# KSS3.net
KiCad netlist of a schematic drawn in Altium Designer
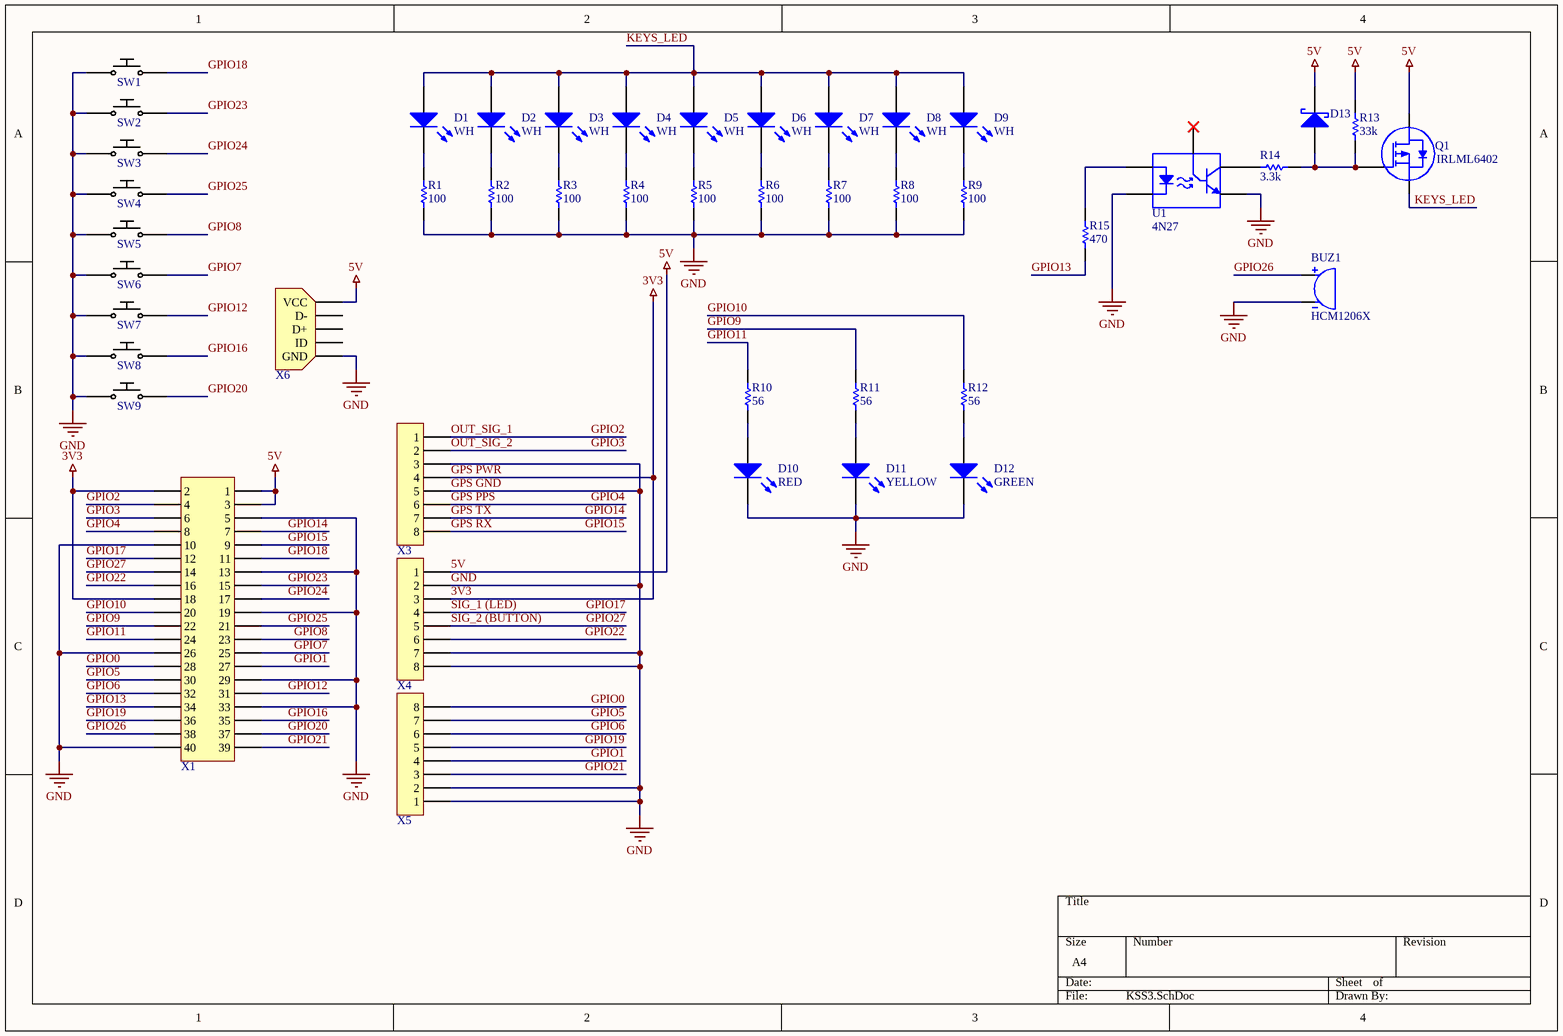
[diagram p0: KSS3.SchDoc]

(export (version "E")
  (design (tool "Eeschema 10.0.6"))
  (components
    (comp (ref "BUZ1")
      (value "HCM1206X")
      (footprint "HCM1206X")
      (description "Buzzer")
      (libsource (lib "COMPONENTS_2022") (part "HCM1206X"))
    )
    (comp (ref "D1")
      (value "WH")
      (footprint "LED_1206")
      (libsource (lib "COMPONENTS_2022") (part "Diode LED"))
    )
    (comp (ref "D2")
      (value "WH")
      (footprint "LED_1206")
      (libsource (lib "COMPONENTS_2022") (part "Diode LED"))
    )
    (comp (ref "D3")
      (value "WH")
      (footprint "LED_1206")
      (libsource (lib "COMPONENTS_2022") (part "Diode LED"))
    )
    (comp (ref "D4")
      (value "WH")
      (footprint "LED_1206")
      (libsource (lib "COMPONENTS_2022") (part "Diode LED"))
    )
    (comp (ref "D5")
      (value "WH")
      (footprint "LED_1206")
      (libsource (lib "COMPONENTS_2022") (part "Diode LED"))
    )
    (comp (ref "D6")
      (value "WH")
      (footprint "LED_1206")
      (libsource (lib "COMPONENTS_2022") (part "Diode LED"))
    )
    (comp (ref "D7")
      (value "WH")
      (footprint "LED_1206")
      (libsource (lib "COMPONENTS_2022") (part "Diode LED"))
    )
    (comp (ref "D8")
      (value "WH")
      (footprint "LED_1206")
      (libsource (lib "COMPONENTS_2022") (part "Diode LED"))
    )
    (comp (ref "D9")
      (value "WH")
      (footprint "LED_1206")
      (libsource (lib "COMPONENTS_2022") (part "Diode LED"))
    )
    (comp (ref "D10")
      (value "RED")
      (footprint "LED_1206")
      (libsource (lib "COMPONENTS_2022") (part "Diode LED"))
    )
    (comp (ref "D11")
      (value "YELLOW")
      (footprint "LED_1206")
      (libsource (lib "COMPONENTS_2022") (part "Diode LED"))
    )
    (comp (ref "D12")
      (value "GREEN")
      (footprint "LED_1206")
      (libsource (lib "COMPONENTS_2022") (part "Diode LED"))
    )
    (comp (ref "D13")
      (value "SS14")
      (footprint "SMA/DO-214AC")
      (description "Schottky")
      (libsource (lib "COMPONENTS_2022") (part "SS14"))
    )
    (comp (ref "Q1")
      (value "IRLML6402")
      (footprint "SOT23_3_PIN")
      (description "P-MOSFET")
      (libsource (lib "COMPONENTS_2022") (part "IRLML6402"))
    )
    (comp (ref "R1")
      (value "Resistor")
      (footprint "RES 1206")
      (fields (field (name "RESISTANCE") "100"))
      (libsource (lib "COMPONENTS_2022") (part "Resistor"))
    )
    (comp (ref "R2")
      (value "Resistor")
      (footprint "RES 1206")
      (fields (field (name "RESISTANCE") "100"))
      (libsource (lib "COMPONENTS_2022") (part "Resistor"))
    )
    (comp (ref "R3")
      (value "Resistor")
      (footprint "RES 1206")
      (fields (field (name "RESISTANCE") "100"))
      (libsource (lib "COMPONENTS_2022") (part "Resistor"))
    )
    (comp (ref "R4")
      (value "Resistor")
      (footprint "RES 1206")
      (fields (field (name "RESISTANCE") "100"))
      (libsource (lib "COMPONENTS_2022") (part "Resistor"))
    )
    (comp (ref "R5")
      (value "Resistor")
      (footprint "RES 1206")
      (fields (field (name "RESISTANCE") "100"))
      (libsource (lib "COMPONENTS_2022") (part "Resistor"))
    )
    (comp (ref "R6")
      (value "Resistor")
      (footprint "RES 1206")
      (fields (field (name "RESISTANCE") "100"))
      (libsource (lib "COMPONENTS_2022") (part "Resistor"))
    )
    (comp (ref "R7")
      (value "Resistor")
      (footprint "RES 1206")
      (fields (field (name "RESISTANCE") "100"))
      (libsource (lib "COMPONENTS_2022") (part "Resistor"))
    )
    (comp (ref "R8")
      (value "Resistor")
      (footprint "RES 1206")
      (fields (field (name "RESISTANCE") "100"))
      (libsource (lib "COMPONENTS_2022") (part "Resistor"))
    )
    (comp (ref "R9")
      (value "Resistor")
      (footprint "RES 1206")
      (fields (field (name "RESISTANCE") "100"))
      (libsource (lib "COMPONENTS_2022") (part "Resistor"))
    )
    (comp (ref "R10")
      (value "Resistor")
      (footprint "RES 1206")
      (fields (field (name "RESISTANCE") "56"))
      (libsource (lib "COMPONENTS_2022") (part "Resistor"))
    )
    (comp (ref "R11")
      (value "Resistor")
      (footprint "RES 1206")
      (fields (field (name "RESISTANCE") "56"))
      (libsource (lib "COMPONENTS_2022") (part "Resistor"))
    )
    (comp (ref "R12")
      (value "Resistor")
      (footprint "RES 1206")
      (fields (field (name "RESISTANCE") "56"))
      (libsource (lib "COMPONENTS_2022") (part "Resistor"))
    )
    (comp (ref "R13")
      (value "Resistor")
      (footprint "RES 1206")
      (fields (field (name "RESISTANCE") "33k"))
      (libsource (lib "COMPONENTS_2022") (part "Resistor"))
    )
    (comp (ref "R14")
      (value "Resistor")
      (footprint "RES 1206")
      (fields (field (name "RESISTANCE") "3.3k"))
      (libsource (lib "COMPONENTS_2022") (part "Resistor"))
    )
    (comp (ref "R15")
      (value "Resistor")
      (footprint "RES 1206")
      (fields (field (name "RESISTANCE") "470"))
      (libsource (lib "COMPONENTS_2022") (part "Resistor"))
    )
    (comp (ref "SW1")
      (value "Pushbutton")
      (footprint "Key switch Outemu")
      (libsource (lib "COMPONENTS_2022") (part "Pushbutton"))
    )
    (comp (ref "SW2")
      (value "Pushbutton")
      (footprint "Key switch Outemu")
      (libsource (lib "COMPONENTS_2022") (part "Pushbutton"))
    )
    (comp (ref "SW3")
      (value "Pushbutton")
      (footprint "Key switch Outemu")
      (libsource (lib "COMPONENTS_2022") (part "Pushbutton"))
    )
    (comp (ref "SW4")
      (value "Pushbutton")
      (footprint "Key switch Outemu")
      (libsource (lib "COMPONENTS_2022") (part "Pushbutton"))
    )
    (comp (ref "SW5")
      (value "Pushbutton")
      (footprint "Key switch Outemu")
      (libsource (lib "COMPONENTS_2022") (part "Pushbutton"))
    )
    (comp (ref "SW6")
      (value "Pushbutton")
      (footprint "Key switch Outemu")
      (libsource (lib "COMPONENTS_2022") (part "Pushbutton"))
    )
    (comp (ref "SW7")
      (value "Pushbutton")
      (footprint "Key switch Outemu")
      (libsource (lib "COMPONENTS_2022") (part "Pushbutton"))
    )
    (comp (ref "SW8")
      (value "Pushbutton")
      (footprint "Key switch Outemu")
      (libsource (lib "COMPONENTS_2022") (part "Pushbutton"))
    )
    (comp (ref "SW9")
      (value "Pushbutton")
      (footprint "Key switch Outemu")
      (libsource (lib "COMPONENTS_2022") (part "Pushbutton"))
    )
    (comp (ref "U1")
      (value "4N27")
      (footprint "DIP6")
      (description "Optocoupler")
      (libsource (lib "COMPONENTS_2022") (part "4N27"))
    )
    (comp (ref "X1")
      (value "GoldPin_F_20x2")
      (footprint "GOLDPIN_F_20x2")
      (libsource (lib "COMPONENTS_2022") (part "GoldPin_F_20x2"))
    )
    (comp (ref "X3")
      (value "?")
      (footprint "SCREW_TERMINAL_X8 5,08mm")
      (libsource (lib "") (part "Connector x8_1"))
    )
    (comp (ref "X4")
      (value "?")
      (footprint "SCREW_TERMINAL_X8 5,08mm")
      (libsource (lib "") (part "Connector x8_1"))
    )
    (comp (ref "X5")
      (value "?")
      (footprint "SCREW_TERMINAL_X8 5,08mm")
      (libsource (lib "COMPONENTS_2022") (part "Connector x8"))
    )
    (comp (ref "X6")
      (value "USB_MICRO_B")
      (footprint "USB_MICRO_B_940 KEYSTONE")
      (libsource (lib "COMPONENTS_2022") (part "USB_MICRO_B"))
    )
  )
  (nets
    (net (code "1") (name "/GPIO0") (class "Default")
      (node (ref "X1") (pin "28") (pinfunction "28_28") (pintype "passive"))
      (node (ref "X5") (pin "8") (pinfunction "8_8") (pintype "passive"))
    )
    (net (code "2") (name "/GPIO1") (class "Default")
      (node (ref "X1") (pin "27") (pinfunction "27_27") (pintype "passive"))
      (node (ref "X5") (pin "4") (pinfunction "4_4") (pintype "passive"))
    )
    (net (code "3") (name "/GPIO2") (class "Default")
      (node (ref "X1") (pin "4") (pinfunction "4_4") (pintype "passive"))
      (node (ref "X3") (pin "1") (pinfunction "1_1") (pintype "passive"))
    )
    (net (code "4") (name "/GPIO3") (class "Default")
      (node (ref "X1") (pin "6") (pinfunction "6_6") (pintype "passive"))
      (node (ref "X3") (pin "2") (pinfunction "2_2") (pintype "passive"))
    )
    (net (code "5") (name "/GPIO4") (class "Default")
      (node (ref "X1") (pin "8") (pinfunction "8_8") (pintype "passive"))
      (node (ref "X3") (pin "6") (pinfunction "6_6") (pintype "passive"))
    )
    (net (code "6") (name "/GPIO5") (class "Default")
      (node (ref "X1") (pin "30") (pinfunction "30_30") (pintype "passive"))
      (node (ref "X5") (pin "7") (pinfunction "7_7") (pintype "passive"))
    )
    (net (code "7") (name "/GPIO6") (class "Default")
      (node (ref "X1") (pin "32") (pinfunction "32_32") (pintype "passive"))
      (node (ref "X5") (pin "6") (pinfunction "6_6") (pintype "passive"))
    )
    (net (code "8") (name "/GPIO7") (class "Default")
      (node (ref "SW6") (pin "2") (pinfunction "2_2") (pintype "passive"))
      (node (ref "X1") (pin "25") (pinfunction "25_25") (pintype "passive"))
    )
    (net (code "9") (name "/GPIO8") (class "Default")
      (node (ref "SW5") (pin "2") (pinfunction "2_2") (pintype "passive"))
      (node (ref "X1") (pin "23") (pinfunction "23_23") (pintype "passive"))
    )
    (net (code "10") (name "/GPIO9") (class "Default")
      (node (ref "R11") (pin "2") (pinfunction "2_2") (pintype "passive"))
      (node (ref "X1") (pin "22") (pinfunction "22_22") (pintype "passive"))
    )
    (net (code "11") (name "/GPIO10") (class "Default")
      (node (ref "R12") (pin "2") (pinfunction "2_2") (pintype "passive"))
      (node (ref "X1") (pin "20") (pinfunction "20_20") (pintype "passive"))
    )
    (net (code "12") (name "/GPIO11") (class "Default")
      (node (ref "R10") (pin "2") (pinfunction "2_2") (pintype "passive"))
      (node (ref "X1") (pin "24") (pinfunction "24_24") (pintype "passive"))
    )
    (net (code "13") (name "/GPIO12") (class "Default")
      (node (ref "SW7") (pin "2") (pinfunction "2_2") (pintype "passive"))
      (node (ref "X1") (pin "31") (pinfunction "31_31") (pintype "passive"))
    )
    (net (code "14") (name "/GPIO13") (class "Default")
      (node (ref "R15") (pin "1") (pinfunction "1_1") (pintype "passive"))
      (node (ref "X1") (pin "34") (pinfunction "34_34") (pintype "passive"))
    )
    (net (code "15") (name "/GPIO14") (class "Default")
      (node (ref "X1") (pin "7") (pinfunction "7_7") (pintype "passive"))
      (node (ref "X3") (pin "7") (pinfunction "7_7") (pintype "passive"))
    )
    (net (code "16") (name "/GPIO15") (class "Default")
      (node (ref "X1") (pin "9") (pinfunction "9_9") (pintype "passive"))
      (node (ref "X3") (pin "8") (pinfunction "8_8") (pintype "passive"))
    )
    (net (code "17") (name "/GPIO16") (class "Default")
      (node (ref "SW8") (pin "2") (pinfunction "2_2") (pintype "passive"))
      (node (ref "X1") (pin "35") (pinfunction "35_35") (pintype "passive"))
    )
    (net (code "18") (name "/GPIO17") (class "Default")
      (node (ref "X1") (pin "12") (pinfunction "12_12") (pintype "passive"))
      (node (ref "X4") (pin "4") (pinfunction "4_4") (pintype "passive"))
    )
    (net (code "19") (name "/GPIO18") (class "Default")
      (node (ref "SW1") (pin "2") (pinfunction "2_2") (pintype "passive"))
      (node (ref "X1") (pin "11") (pinfunction "11_11") (pintype "passive"))
    )
    (net (code "20") (name "/GPIO19") (class "Default")
      (node (ref "X1") (pin "36") (pinfunction "36_36") (pintype "passive"))
      (node (ref "X5") (pin "5") (pinfunction "5_5") (pintype "passive"))
    )
    (net (code "21") (name "/GPIO20") (class "Default")
      (node (ref "SW9") (pin "2") (pinfunction "2_2") (pintype "passive"))
      (node (ref "X1") (pin "37") (pinfunction "37_37") (pintype "passive"))
    )
    (net (code "22") (name "/GPIO21") (class "Default")
      (node (ref "X1") (pin "39") (pinfunction "39_39") (pintype "passive"))
      (node (ref "X5") (pin "3") (pinfunction "3_3") (pintype "passive"))
    )
    (net (code "23") (name "/GPIO22") (class "Default")
      (node (ref "X1") (pin "16") (pinfunction "16_16") (pintype "passive"))
      (node (ref "X4") (pin "6") (pinfunction "6_6") (pintype "passive"))
    )
    (net (code "24") (name "/GPIO23") (class "Default")
      (node (ref "SW2") (pin "2") (pinfunction "2_2") (pintype "passive"))
      (node (ref "X1") (pin "15") (pinfunction "15_15") (pintype "passive"))
    )
    (net (code "25") (name "/GPIO24") (class "Default")
      (node (ref "SW3") (pin "2") (pinfunction "2_2") (pintype "passive"))
      (node (ref "X1") (pin "17") (pinfunction "17_17") (pintype "passive"))
    )
    (net (code "26") (name "/GPIO25") (class "Default")
      (node (ref "SW4") (pin "2") (pinfunction "2_2") (pintype "passive"))
      (node (ref "X1") (pin "21") (pinfunction "21_21") (pintype "passive"))
    )
    (net (code "27") (name "/GPIO26") (class "Default")
      (node (ref "BUZ1") (pin "1") (pinfunction "+_1") (pintype "passive"))
      (node (ref "X1") (pin "38") (pinfunction "38_38") (pintype "passive"))
    )
    (net (code "28") (name "/GPIO27") (class "Default")
      (node (ref "X1") (pin "14") (pinfunction "14_14") (pintype "passive"))
      (node (ref "X4") (pin "5") (pinfunction "5_5") (pintype "passive"))
    )
    (net (code "29") (name "/KEYS_LED") (class "Default")
      (node (ref "D1") (pin "1") (pinfunction "A_1") (pintype "passive"))
      (node (ref "D2") (pin "1") (pinfunction "A_1") (pintype "passive"))
      (node (ref "D3") (pin "1") (pinfunction "A_1") (pintype "passive"))
      (node (ref "D4") (pin "1") (pinfunction "A_1") (pintype "passive"))
      (node (ref "D5") (pin "1") (pinfunction "A_1") (pintype "passive"))
      (node (ref "D6") (pin "1") (pinfunction "A_1") (pintype "passive"))
      (node (ref "D7") (pin "1") (pinfunction "A_1") (pintype "passive"))
      (node (ref "D8") (pin "1") (pinfunction "A_1") (pintype "passive"))
      (node (ref "D9") (pin "1") (pinfunction "A_1") (pintype "passive"))
      (node (ref "Q1") (pin "2") (pinfunction "S_2") (pintype "passive"))
    )
    (net (code "30") (name "3V3") (class "Default")
      (node (ref "X1") (pin "18") (pinfunction "18_18") (pintype "passive"))
      (node (ref "X1") (pin "2") (pinfunction "2_2") (pintype "passive"))
      (node (ref "X3") (pin "4") (pinfunction "4_4") (pintype "passive"))
      (node (ref "X4") (pin "3") (pinfunction "3_3") (pintype "passive"))
    )
    (net (code "31") (name "5V") (class "Default")
      (node (ref "D13") (pin "2") (pinfunction "K_2") (pintype "passive"))
      (node (ref "Q1") (pin "3") (pinfunction "D_3") (pintype "passive"))
      (node (ref "R13") (pin "1") (pinfunction "1_1") (pintype "passive"))
      (node (ref "X1") (pin "1") (pinfunction "1_1") (pintype "passive"))
      (node (ref "X1") (pin "3") (pinfunction "3_3") (pintype "passive"))
      (node (ref "X4") (pin "1") (pinfunction "1_1") (pintype "passive"))
      (node (ref "X6") (pin "1") (pinfunction "VCC_1") (pintype "passive"))
    )
    (net (code "32") (name "GND") (class "Default")
      (node (ref "BUZ1") (pin "2") (pinfunction "-_2") (pintype "passive"))
      (node (ref "D10") (pin "2") (pinfunction "K_2") (pintype "passive"))
      (node (ref "D11") (pin "2") (pinfunction "K_2") (pintype "passive"))
      (node (ref "D12") (pin "2") (pinfunction "K_2") (pintype "passive"))
      (node (ref "R1") (pin "1") (pinfunction "1_1") (pintype "passive"))
      (node (ref "R2") (pin "1") (pinfunction "1_1") (pintype "passive"))
      (node (ref "R3") (pin "1") (pinfunction "1_1") (pintype "passive"))
      (node (ref "R4") (pin "1") (pinfunction "1_1") (pintype "passive"))
      (node (ref "R5") (pin "1") (pinfunction "1_1") (pintype "passive"))
      (node (ref "R6") (pin "1") (pinfunction "1_1") (pintype "passive"))
      (node (ref "R7") (pin "1") (pinfunction "1_1") (pintype "passive"))
      (node (ref "R8") (pin "1") (pinfunction "1_1") (pintype "passive"))
      (node (ref "R9") (pin "1") (pinfunction "1_1") (pintype "passive"))
      (node (ref "SW1") (pin "1") (pinfunction "1_1") (pintype "passive"))
      (node (ref "SW2") (pin "1") (pinfunction "1_1") (pintype "passive"))
      (node (ref "SW3") (pin "1") (pinfunction "1_1") (pintype "passive"))
      (node (ref "SW4") (pin "1") (pinfunction "1_1") (pintype "passive"))
      (node (ref "SW5") (pin "1") (pinfunction "1_1") (pintype "passive"))
      (node (ref "SW6") (pin "1") (pinfunction "1_1") (pintype "passive"))
      (node (ref "SW7") (pin "1") (pinfunction "1_1") (pintype "passive"))
      (node (ref "SW8") (pin "1") (pinfunction "1_1") (pintype "passive"))
      (node (ref "SW9") (pin "1") (pinfunction "1_1") (pintype "passive"))
      (node (ref "U1") (pin "2") (pinfunction "K_2") (pintype "passive"))
      (node (ref "U1") (pin "4") (pinfunction "E_4") (pintype "passive"))
      (node (ref "X1") (pin "10") (pinfunction "10_10") (pintype "passive"))
      (node (ref "X1") (pin "13") (pinfunction "13_13") (pintype "passive"))
      (node (ref "X1") (pin "19") (pinfunction "19_19") (pintype "passive"))
      (node (ref "X1") (pin "26") (pinfunction "26_26") (pintype "passive"))
      (node (ref "X1") (pin "29") (pinfunction "29_29") (pintype "passive"))
      (node (ref "X1") (pin "33") (pinfunction "33_33") (pintype "passive"))
      (node (ref "X1") (pin "40") (pinfunction "40_40") (pintype "passive"))
      (node (ref "X1") (pin "5") (pinfunction "5_5") (pintype "passive"))
      (node (ref "X3") (pin "3") (pinfunction "3_3") (pintype "passive"))
      (node (ref "X3") (pin "5") (pinfunction "5_5") (pintype "passive"))
      (node (ref "X4") (pin "2") (pinfunction "2_2") (pintype "passive"))
      (node (ref "X4") (pin "7") (pinfunction "7_7") (pintype "passive"))
      (node (ref "X4") (pin "8") (pinfunction "8_8") (pintype "passive"))
      (node (ref "X5") (pin "1") (pinfunction "1_1") (pintype "passive"))
      (node (ref "X5") (pin "2") (pinfunction "2_2") (pintype "passive"))
      (node (ref "X6") (pin "5") (pinfunction "GND_5") (pintype "passive"))
    )
    (net (code "33") (name "Net-(D1-K)") (class "Default")
      (node (ref "D1") (pin "2") (pinfunction "K_2") (pintype "passive"))
      (node (ref "R1") (pin "2") (pinfunction "2_2") (pintype "passive"))
    )
    (net (code "34") (name "Net-(D2-K)") (class "Default")
      (node (ref "D2") (pin "2") (pinfunction "K_2") (pintype "passive"))
      (node (ref "R2") (pin "2") (pinfunction "2_2") (pintype "passive"))
    )
    (net (code "35") (name "Net-(D3-K)") (class "Default")
      (node (ref "D3") (pin "2") (pinfunction "K_2") (pintype "passive"))
      (node (ref "R3") (pin "2") (pinfunction "2_2") (pintype "passive"))
    )
    (net (code "36") (name "Net-(D4-K)") (class "Default")
      (node (ref "D4") (pin "2") (pinfunction "K_2") (pintype "passive"))
      (node (ref "R4") (pin "2") (pinfunction "2_2") (pintype "passive"))
    )
    (net (code "37") (name "Net-(D5-K)") (class "Default")
      (node (ref "D5") (pin "2") (pinfunction "K_2") (pintype "passive"))
      (node (ref "R5") (pin "2") (pinfunction "2_2") (pintype "passive"))
    )
    (net (code "38") (name "Net-(D6-K)") (class "Default")
      (node (ref "D6") (pin "2") (pinfunction "K_2") (pintype "passive"))
      (node (ref "R6") (pin "2") (pinfunction "2_2") (pintype "passive"))
    )
    (net (code "39") (name "Net-(D7-K)") (class "Default")
      (node (ref "D7") (pin "2") (pinfunction "K_2") (pintype "passive"))
      (node (ref "R7") (pin "2") (pinfunction "2_2") (pintype "passive"))
    )
    (net (code "40") (name "Net-(D8-K)") (class "Default")
      (node (ref "D8") (pin "2") (pinfunction "K_2") (pintype "passive"))
      (node (ref "R8") (pin "2") (pinfunction "2_2") (pintype "passive"))
    )
    (net (code "41") (name "Net-(D9-K)") (class "Default")
      (node (ref "D9") (pin "2") (pinfunction "K_2") (pintype "passive"))
      (node (ref "R9") (pin "2") (pinfunction "2_2") (pintype "passive"))
    )
    (net (code "42") (name "Net-(D10-A)") (class "Default")
      (node (ref "D10") (pin "1") (pinfunction "A_1") (pintype "passive"))
      (node (ref "R10") (pin "1") (pinfunction "1_1") (pintype "passive"))
    )
    (net (code "43") (name "Net-(D11-A)") (class "Default")
      (node (ref "D11") (pin "1") (pinfunction "A_1") (pintype "passive"))
      (node (ref "R11") (pin "1") (pinfunction "1_1") (pintype "passive"))
    )
    (net (code "44") (name "Net-(D12-A)") (class "Default")
      (node (ref "D12") (pin "1") (pinfunction "A_1") (pintype "passive"))
      (node (ref "R12") (pin "1") (pinfunction "1_1") (pintype "passive"))
    )
    (net (code "45") (name "Net-(D13-A)") (class "Default")
      (node (ref "D13") (pin "1") (pinfunction "A_1") (pintype "passive"))
      (node (ref "Q1") (pin "1") (pinfunction "G_1") (pintype "passive"))
      (node (ref "R13") (pin "2") (pinfunction "2_2") (pintype "passive"))
      (node (ref "R14") (pin "2") (pinfunction "2_2") (pintype "passive"))
    )
    (net (code "46") (name "Net-(U1-A)") (class "Default")
      (node (ref "R15") (pin "2") (pinfunction "2_2") (pintype "passive"))
      (node (ref "U1") (pin "1") (pinfunction "A_1") (pintype "passive"))
    )
    (net (code "47") (name "Net-(U1-C)") (class "Default")
      (node (ref "R14") (pin "1") (pinfunction "1_1") (pintype "passive"))
      (node (ref "U1") (pin "5") (pinfunction "C_5") (pintype "passive"))
    )
    (net (code "48") (name "unconnected-(U1-B-Pad6)") (class "Default")
      (node (ref "U1") (pin "6") (pinfunction "B_6") (pintype "passive+no_connect"))
    )
    (net (code "49") (name "unconnected-(X6-D+-Pad3)") (class "Default")
      (node (ref "X6") (pin "3") (pinfunction "D+_3") (pintype "passive"))
    )
    (net (code "50") (name "unconnected-(X6-D--Pad2)") (class "Default")
      (node (ref "X6") (pin "2") (pinfunction "D-_2") (pintype "passive"))
    )
    (net (code "51") (name "unconnected-(X6-ID-Pad4)") (class "Default")
      (node (ref "X6") (pin "4") (pinfunction "ID_4") (pintype "passive"))
    )
  )
)
